# MachXO3D-QFN72-breakout.net
KiCad netlist of a schematic drawn in Altium Designer
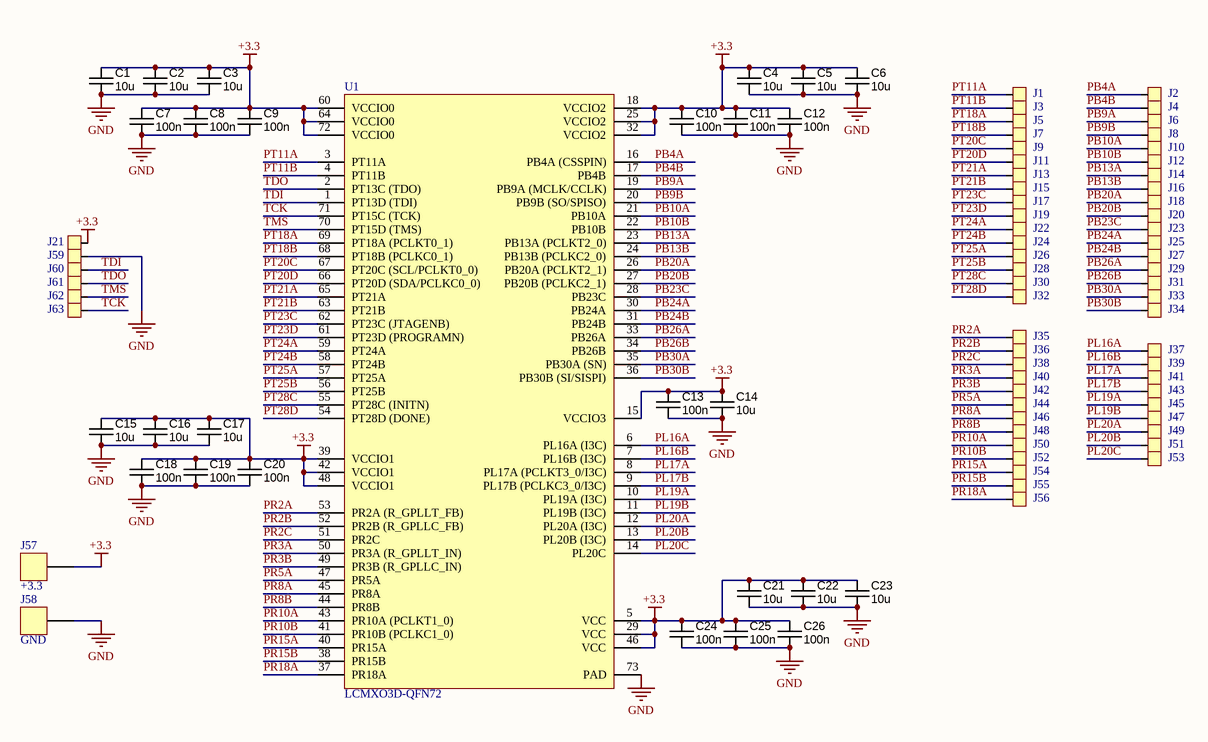
[diagram p0: MachXO3D-QFN72-breakout.SchDoc]

(export (version "E")
  (design (tool "Eeschema 10.0.6"))
  (components
    (comp (ref "C1")
      (value "10u")
      (footprint "CAPC1005X55N")
      (description "Capacitor SMD Cer 1uF 10% 16V X5R 0402")
      (fields (field (name "TOLERANCE") "±10%"))
      (libsource (lib "PBL - Capacitors") (part "CAPC_1u_0402_X5R_6V3_10%"))
    )
    (comp (ref "C2")
      (value "10u")
      (footprint "CAPC1005X55N")
      (description "Capacitor SMD Cer 1uF 10% 16V X5R 0402")
      (fields (field (name "TOLERANCE") "±10%"))
      (libsource (lib "PBL - Capacitors") (part "CAPC_1u_0402_X5R_6V3_10%"))
    )
    (comp (ref "C3")
      (value "10u")
      (footprint "CAPC1005X55N")
      (description "Capacitor SMD Cer 1uF 10% 16V X5R 0402")
      (fields (field (name "TOLERANCE") "±10%"))
      (libsource (lib "PBL - Capacitors") (part "CAPC_1u_0402_X5R_6V3_10%"))
    )
    (comp (ref "C4")
      (value "10u")
      (footprint "CAPC1005X55N")
      (description "Capacitor SMD Cer 1uF 10% 16V X5R 0402")
      (fields (field (name "TOLERANCE") "±10%"))
      (libsource (lib "PBL - Capacitors") (part "CAPC_1u_0402_X5R_6V3_10%"))
    )
    (comp (ref "C5")
      (value "10u")
      (footprint "CAPC1005X55N")
      (description "Capacitor SMD Cer 1uF 10% 16V X5R 0402")
      (fields (field (name "TOLERANCE") "±10%"))
      (libsource (lib "PBL - Capacitors") (part "CAPC_1u_0402_X5R_6V3_10%"))
    )
    (comp (ref "C6")
      (value "10u")
      (footprint "CAPC1005X55N")
      (description "Capacitor SMD Cer 1uF 10% 16V X5R 0402")
      (fields (field (name "TOLERANCE") "±10%"))
      (libsource (lib "PBL - Capacitors") (part "CAPC_1u_0402_X5R_6V3_10%"))
    )
    (comp (ref "C7")
      (value "100n")
      (footprint "CAPC0603X04N")
      (fields (field (name "Comment") "CAPC_100n_0201"))
      (libsource (lib "passive") (part "CAPC_100n_0201"))
    )
    (comp (ref "C8")
      (value "100n")
      (footprint "CAPC0603X04N")
      (fields (field (name "Comment") "CAPC_100n_0201"))
      (libsource (lib "passive") (part "CAPC_100n_0201"))
    )
    (comp (ref "C9")
      (value "100n")
      (footprint "CAPC0603X04N")
      (fields (field (name "Comment") "CAPC_100n_0201"))
      (libsource (lib "passive") (part "CAPC_100n_0201"))
    )
    (comp (ref "C10")
      (value "100n")
      (footprint "CAPC0603X04N")
      (fields (field (name "Comment") "CAPC_100n_0201"))
      (libsource (lib "passive") (part "CAPC_100n_0201"))
    )
    (comp (ref "C11")
      (value "100n")
      (footprint "CAPC0603X04N")
      (fields (field (name "Comment") "CAPC_100n_0201"))
      (libsource (lib "passive") (part "CAPC_100n_0201"))
    )
    (comp (ref "C12")
      (value "100n")
      (footprint "CAPC0603X04N")
      (fields (field (name "Comment") "CAPC_100n_0201"))
      (libsource (lib "passive") (part "CAPC_100n_0201"))
    )
    (comp (ref "C13")
      (value "100n")
      (footprint "CAPC0603X04N")
      (fields (field (name "Comment") "CAPC_100n_0201"))
      (libsource (lib "passive") (part "CAPC_100n_0201"))
    )
    (comp (ref "C14")
      (value "10u")
      (footprint "CAPC1005X55N")
      (description "Capacitor SMD Cer 1uF 10% 16V X5R 0402")
      (fields (field (name "TOLERANCE") "±10%"))
      (libsource (lib "PBL - Capacitors") (part "CAPC_1u_0402_X5R_6V3_10%"))
    )
    (comp (ref "C15")
      (value "10u")
      (footprint "CAPC1005X55N")
      (description "Capacitor SMD Cer 1uF 10% 16V X5R 0402")
      (fields (field (name "TOLERANCE") "±10%"))
      (libsource (lib "PBL - Capacitors") (part "CAPC_1u_0402_X5R_6V3_10%"))
    )
    (comp (ref "C16")
      (value "10u")
      (footprint "CAPC1005X55N")
      (description "Capacitor SMD Cer 1uF 10% 16V X5R 0402")
      (fields (field (name "TOLERANCE") "±10%"))
      (libsource (lib "PBL - Capacitors") (part "CAPC_1u_0402_X5R_6V3_10%"))
    )
    (comp (ref "C17")
      (value "10u")
      (footprint "CAPC1005X55N")
      (description "Capacitor SMD Cer 1uF 10% 16V X5R 0402")
      (fields (field (name "TOLERANCE") "±10%"))
      (libsource (lib "PBL - Capacitors") (part "CAPC_1u_0402_X5R_6V3_10%"))
    )
    (comp (ref "C18")
      (value "100n")
      (footprint "CAPC0603X04N")
      (fields (field (name "Comment") "CAPC_100n_0201"))
      (libsource (lib "passive") (part "CAPC_100n_0201"))
    )
    (comp (ref "C19")
      (value "100n")
      (footprint "CAPC0603X04N")
      (fields (field (name "Comment") "CAPC_100n_0201"))
      (libsource (lib "passive") (part "CAPC_100n_0201"))
    )
    (comp (ref "C20")
      (value "100n")
      (footprint "CAPC0603X04N")
      (fields (field (name "Comment") "CAPC_100n_0201"))
      (libsource (lib "passive") (part "CAPC_100n_0201"))
    )
    (comp (ref "C21")
      (value "10u")
      (footprint "CAPC1005X55N")
      (description "Capacitor SMD Cer 1uF 10% 16V X5R 0402")
      (fields (field (name "TOLERANCE") "±10%"))
      (libsource (lib "PBL - Capacitors") (part "CAPC_1u_0402_X5R_6V3_10%"))
    )
    (comp (ref "C22")
      (value "10u")
      (footprint "CAPC1005X55N")
      (description "Capacitor SMD Cer 1uF 10% 16V X5R 0402")
      (fields (field (name "TOLERANCE") "±10%"))
      (libsource (lib "PBL - Capacitors") (part "CAPC_1u_0402_X5R_6V3_10%"))
    )
    (comp (ref "C23")
      (value "10u")
      (footprint "CAPC1005X55N")
      (description "Capacitor SMD Cer 1uF 10% 16V X5R 0402")
      (fields (field (name "TOLERANCE") "±10%"))
      (libsource (lib "PBL - Capacitors") (part "CAPC_1u_0402_X5R_6V3_10%"))
    )
    (comp (ref "C24")
      (value "100n")
      (footprint "CAPC0603X04N")
      (fields (field (name "Comment") "CAPC_100n_0201"))
      (libsource (lib "passive") (part "CAPC_100n_0201"))
    )
    (comp (ref "C25")
      (value "100n")
      (footprint "CAPC0603X04N")
      (fields (field (name "Comment") "CAPC_100n_0201"))
      (libsource (lib "passive") (part "CAPC_100n_0201"))
    )
    (comp (ref "C26")
      (value "100n")
      (footprint "CAPC0603X04N")
      (fields (field (name "Comment") "CAPC_100n_0201"))
      (libsource (lib "passive") (part "CAPC_100n_0201"))
    )
    (comp (ref "J1") (value "T11A") (footprint "PAD-1020") (libsource (lib "connectors") (part "SOLDER-PAD")))
    (comp (ref "J2") (value "B4A") (footprint "PAD-1020") (libsource (lib "connectors") (part "SOLDER-PAD")))
    (comp (ref "J3") (value "T11B") (footprint "PAD-1020") (libsource (lib "connectors") (part "SOLDER-PAD")))
    (comp (ref "J4") (value "B4B") (footprint "PAD-1020") (libsource (lib "connectors") (part "SOLDER-PAD")))
    (comp (ref "J5") (value "T18A") (footprint "PAD-1020") (libsource (lib "connectors") (part "SOLDER-PAD")))
    (comp (ref "J6") (value "B9A") (footprint "PAD-1020") (libsource (lib "connectors") (part "SOLDER-PAD")))
    (comp (ref "J7") (value "T18B") (footprint "PAD-1020") (libsource (lib "connectors") (part "SOLDER-PAD")))
    (comp (ref "J8") (value "B9B") (footprint "PAD-1020") (libsource (lib "connectors") (part "SOLDER-PAD")))
    (comp (ref "J9") (value "T20C") (footprint "PAD-1020") (libsource (lib "connectors") (part "SOLDER-PAD")))
    (comp (ref "J10")
      (value "B10A")
      (footprint "PAD-1020")
      (libsource (lib "connectors") (part "SOLDER-PAD"))
    )
    (comp (ref "J11")
      (value "T20D")
      (footprint "PAD-1020")
      (libsource (lib "connectors") (part "SOLDER-PAD"))
    )
    (comp (ref "J12")
      (value "B10B")
      (footprint "PAD-1020")
      (libsource (lib "connectors") (part "SOLDER-PAD"))
    )
    (comp (ref "J13")
      (value "T21A")
      (footprint "PAD-1020")
      (libsource (lib "connectors") (part "SOLDER-PAD"))
    )
    (comp (ref "J14")
      (value "B13A")
      (footprint "PAD-1020")
      (libsource (lib "connectors") (part "SOLDER-PAD"))
    )
    (comp (ref "J15")
      (value "T21B")
      (footprint "PAD-1020")
      (libsource (lib "connectors") (part "SOLDER-PAD"))
    )
    (comp (ref "J16")
      (value "B13B")
      (footprint "PAD-1020")
      (libsource (lib "connectors") (part "SOLDER-PAD"))
    )
    (comp (ref "J17")
      (value "T23C")
      (footprint "PAD-1020")
      (libsource (lib "connectors") (part "SOLDER-PAD"))
    )
    (comp (ref "J18")
      (value "B20A")
      (footprint "PAD-1020")
      (libsource (lib "connectors") (part "SOLDER-PAD"))
    )
    (comp (ref "J19")
      (value "T23D")
      (footprint "PAD-1020")
      (libsource (lib "connectors") (part "SOLDER-PAD"))
    )
    (comp (ref "J20")
      (value "B20B")
      (footprint "PAD-1020")
      (libsource (lib "connectors") (part "SOLDER-PAD"))
    )
    (comp (ref "J21") (value "+3.3") (footprint "PAD-1020") (libsource (lib "") (part "SOLDER-PAD_1")))
    (comp (ref "J22")
      (value "T24A")
      (footprint "PAD-1020")
      (libsource (lib "connectors") (part "SOLDER-PAD"))
    )
    (comp (ref "J23")
      (value "B23C")
      (footprint "PAD-1020")
      (libsource (lib "connectors") (part "SOLDER-PAD"))
    )
    (comp (ref "J24")
      (value "T24B")
      (footprint "PAD-1020")
      (libsource (lib "connectors") (part "SOLDER-PAD"))
    )
    (comp (ref "J25")
      (value "B24A")
      (footprint "PAD-1020")
      (libsource (lib "connectors") (part "SOLDER-PAD"))
    )
    (comp (ref "J26")
      (value "T25A")
      (footprint "PAD-1020")
      (libsource (lib "connectors") (part "SOLDER-PAD"))
    )
    (comp (ref "J27")
      (value "B24B")
      (footprint "PAD-1020")
      (libsource (lib "connectors") (part "SOLDER-PAD"))
    )
    (comp (ref "J28")
      (value "T25B")
      (footprint "PAD-1020")
      (libsource (lib "connectors") (part "SOLDER-PAD"))
    )
    (comp (ref "J29")
      (value "B26A")
      (footprint "PAD-1020")
      (libsource (lib "connectors") (part "SOLDER-PAD"))
    )
    (comp (ref "J30")
      (value "T28C")
      (footprint "PAD-1020")
      (libsource (lib "connectors") (part "SOLDER-PAD"))
    )
    (comp (ref "J31")
      (value "B26B")
      (footprint "PAD-1020")
      (libsource (lib "connectors") (part "SOLDER-PAD"))
    )
    (comp (ref "J32")
      (value "T28D")
      (footprint "PAD-1020")
      (libsource (lib "connectors") (part "SOLDER-PAD"))
    )
    (comp (ref "J33")
      (value "B30A")
      (footprint "PAD-1020")
      (libsource (lib "connectors") (part "SOLDER-PAD"))
    )
    (comp (ref "J34")
      (value "B30B")
      (footprint "PAD-1020")
      (libsource (lib "connectors") (part "SOLDER-PAD"))
    )
    (comp (ref "J35") (value "R2A") (footprint "PAD-1020") (libsource (lib "connectors") (part "SOLDER-PAD")))
    (comp (ref "J36") (value "R2B") (footprint "PAD-1020") (libsource (lib "connectors") (part "SOLDER-PAD")))
    (comp (ref "J37")
      (value "L16A")
      (footprint "PAD-1020")
      (libsource (lib "connectors") (part "SOLDER-PAD"))
    )
    (comp (ref "J38") (value "R2C") (footprint "PAD-1020") (libsource (lib "connectors") (part "SOLDER-PAD")))
    (comp (ref "J39")
      (value "L16B")
      (footprint "PAD-1020")
      (libsource (lib "connectors") (part "SOLDER-PAD"))
    )
    (comp (ref "J40") (value "R3A") (footprint "PAD-1020") (libsource (lib "connectors") (part "SOLDER-PAD")))
    (comp (ref "J41")
      (value "L17A")
      (footprint "PAD-1020")
      (libsource (lib "connectors") (part "SOLDER-PAD"))
    )
    (comp (ref "J42") (value "R3A") (footprint "PAD-1020") (libsource (lib "connectors") (part "SOLDER-PAD")))
    (comp (ref "J43")
      (value "L17B")
      (footprint "PAD-1020")
      (libsource (lib "connectors") (part "SOLDER-PAD"))
    )
    (comp (ref "J44") (value "R5A") (footprint "PAD-1020") (libsource (lib "connectors") (part "SOLDER-PAD")))
    (comp (ref "J45")
      (value "L19A")
      (footprint "PAD-1020")
      (libsource (lib "connectors") (part "SOLDER-PAD"))
    )
    (comp (ref "J46") (value "R8A") (footprint "PAD-1020") (libsource (lib "connectors") (part "SOLDER-PAD")))
    (comp (ref "J47")
      (value "L19B")
      (footprint "PAD-1020")
      (libsource (lib "connectors") (part "SOLDER-PAD"))
    )
    (comp (ref "J48") (value "R8B") (footprint "PAD-1020") (libsource (lib "connectors") (part "SOLDER-PAD")))
    (comp (ref "J49")
      (value "L20A")
      (footprint "PAD-1020")
      (libsource (lib "connectors") (part "SOLDER-PAD"))
    )
    (comp (ref "J50")
      (value "R10A")
      (footprint "PAD-1020")
      (libsource (lib "connectors") (part "SOLDER-PAD"))
    )
    (comp (ref "J51")
      (value "L20B")
      (footprint "PAD-1020")
      (libsource (lib "connectors") (part "SOLDER-PAD"))
    )
    (comp (ref "J52")
      (value "R10B")
      (footprint "PAD-1020")
      (libsource (lib "connectors") (part "SOLDER-PAD"))
    )
    (comp (ref "J53")
      (value "L20C")
      (footprint "PAD-1020")
      (libsource (lib "connectors") (part "SOLDER-PAD"))
    )
    (comp (ref "J54")
      (value "R15A")
      (footprint "PAD-1020")
      (libsource (lib "connectors") (part "SOLDER-PAD"))
    )
    (comp (ref "J55")
      (value "R15B")
      (footprint "PAD-1020")
      (libsource (lib "connectors") (part "SOLDER-PAD"))
    )
    (comp (ref "J56")
      (value "R18A")
      (footprint "PAD-1020")
      (libsource (lib "connectors") (part "SOLDER-PAD"))
    )
    (comp (ref "J57")
      (value "+3.3")
      (footprint "POWER-PAD-4x3")
      (libsource (lib "connectors") (part "HEADER-1"))
    )
    (comp (ref "J58")
      (value "GND")
      (footprint "POWER-PAD-4x3")
      (libsource (lib "connectors") (part "HEADER-1"))
    )
    (comp (ref "J59") (value "GND") (footprint "PAD-1020") (libsource (lib "") (part "SOLDER-PAD_1")))
    (comp (ref "J60") (value "TDI") (footprint "PAD-1020") (libsource (lib "") (part "SOLDER-PAD_1")))
    (comp (ref "J61") (value "TDO") (footprint "PAD-1020") (libsource (lib "") (part "SOLDER-PAD_1")))
    (comp (ref "J62") (value "TMS") (footprint "PAD-1020") (libsource (lib "") (part "SOLDER-PAD_1")))
    (comp (ref "J63") (value "TCK") (footprint "PAD-1020") (libsource (lib "") (part "SOLDER-PAD_1")))
    (comp (ref "U1")
      (value "LCMXO3D-QFN72")
      (footprint "MachXO3D-QFN72")
      (libsource (lib "lattice") (part "LCMXO3D-QFN72"))
    )
  )
  (nets
    (net (code "1") (name "+3.3") (class "Default")
      (node (ref "C1") (pin "1") (pintype "passive"))
      (node (ref "C10") (pin "2") (pinfunction "2_2") (pintype "passive"))
      (node (ref "C11") (pin "2") (pinfunction "2_2") (pintype "passive"))
      (node (ref "C12") (pin "2") (pinfunction "2_2") (pintype "passive"))
      (node (ref "C13") (pin "2") (pinfunction "2_2") (pintype "passive"))
      (node (ref "C14") (pin "1") (pintype "passive"))
      (node (ref "C15") (pin "1") (pintype "passive"))
      (node (ref "C16") (pin "1") (pintype "passive"))
      (node (ref "C17") (pin "1") (pintype "passive"))
      (node (ref "C18") (pin "2") (pinfunction "2_2") (pintype "passive"))
      (node (ref "C19") (pin "2") (pinfunction "2_2") (pintype "passive"))
      (node (ref "C2") (pin "1") (pintype "passive"))
      (node (ref "C20") (pin "2") (pinfunction "2_2") (pintype "passive"))
      (node (ref "C21") (pin "1") (pintype "passive"))
      (node (ref "C22") (pin "1") (pintype "passive"))
      (node (ref "C23") (pin "1") (pintype "passive"))
      (node (ref "C24") (pin "2") (pinfunction "2_2") (pintype "passive"))
      (node (ref "C25") (pin "2") (pinfunction "2_2") (pintype "passive"))
      (node (ref "C26") (pin "2") (pinfunction "2_2") (pintype "passive"))
      (node (ref "C3") (pin "1") (pintype "passive"))
      (node (ref "C4") (pin "1") (pintype "passive"))
      (node (ref "C5") (pin "1") (pintype "passive"))
      (node (ref "C6") (pin "1") (pintype "passive"))
      (node (ref "C7") (pin "2") (pinfunction "2_2") (pintype "passive"))
      (node (ref "C8") (pin "2") (pinfunction "2_2") (pintype "passive"))
      (node (ref "C9") (pin "2") (pinfunction "2_2") (pintype "passive"))
      (node (ref "J21") (pin "1") (pinfunction "1_1") (pintype "passive"))
      (node (ref "J57") (pin "1") (pinfunction "1_1") (pintype "passive"))
      (node (ref "U1") (pin "15") (pinfunction "VCCIO3_15") (pintype "passive"))
      (node (ref "U1") (pin "18") (pinfunction "VCCIO2_18") (pintype "passive"))
      (node (ref "U1") (pin "25") (pinfunction "VCCIO2_25") (pintype "passive"))
      (node (ref "U1") (pin "29") (pinfunction "VCC_29") (pintype "passive"))
      (node (ref "U1") (pin "32") (pinfunction "VCCIO2_32") (pintype "passive"))
      (node (ref "U1") (pin "39") (pinfunction "VCCIO1_39") (pintype "passive"))
      (node (ref "U1") (pin "42") (pinfunction "VCCIO1_42") (pintype "passive"))
      (node (ref "U1") (pin "46") (pinfunction "VCC_46") (pintype "passive"))
      (node (ref "U1") (pin "48") (pinfunction "VCCIO1_48") (pintype "passive"))
      (node (ref "U1") (pin "5") (pinfunction "VCC_5") (pintype "passive"))
      (node (ref "U1") (pin "60") (pinfunction "VCCIO0_60") (pintype "passive"))
      (node (ref "U1") (pin "64") (pinfunction "VCCIO0_64") (pintype "passive"))
      (node (ref "U1") (pin "72") (pinfunction "VCCIO0_72") (pintype "passive"))
    )
    (net (code "2") (name "/PB4A") (class "Default")
      (node (ref "J2") (pin "1") (pinfunction "1_1") (pintype "passive"))
      (node (ref "U1") (pin "16") (pinfunction "PB4A_(CSSPIN)_16") (pintype "passive"))
    )
    (net (code "3") (name "/PB4B") (class "Default")
      (node (ref "J4") (pin "1") (pinfunction "1_1") (pintype "passive"))
      (node (ref "U1") (pin "17") (pinfunction "PB4B_17") (pintype "passive"))
    )
    (net (code "4") (name "/PB9A") (class "Default")
      (node (ref "J6") (pin "1") (pinfunction "1_1") (pintype "passive"))
      (node (ref "U1") (pin "19") (pinfunction "PB9A_(MCLK/CCLK)_19") (pintype "passive"))
    )
    (net (code "5") (name "/PB9B") (class "Default")
      (node (ref "J8") (pin "1") (pinfunction "1_1") (pintype "passive"))
      (node (ref "U1") (pin "20") (pinfunction "PB9B_(SO/SPISO)_20") (pintype "passive"))
    )
    (net (code "6") (name "/PB10A") (class "Default")
      (node (ref "J10") (pin "1") (pinfunction "1_1") (pintype "passive"))
      (node (ref "U1") (pin "21") (pinfunction "PB10A_21") (pintype "passive"))
    )
    (net (code "7") (name "/PB10B") (class "Default")
      (node (ref "J12") (pin "1") (pinfunction "1_1") (pintype "passive"))
      (node (ref "U1") (pin "22") (pinfunction "PB10B_22") (pintype "passive"))
    )
    (net (code "8") (name "/PB13A") (class "Default")
      (node (ref "J14") (pin "1") (pinfunction "1_1") (pintype "passive"))
      (node (ref "U1") (pin "23") (pinfunction "PB13A_(PCLKT2_0)_23") (pintype "passive"))
    )
    (net (code "9") (name "/PB13B") (class "Default")
      (node (ref "J16") (pin "1") (pinfunction "1_1") (pintype "passive"))
      (node (ref "U1") (pin "24") (pinfunction "PB13B_(PCLKC2_0)_24") (pintype "passive"))
    )
    (net (code "10") (name "/PB20A") (class "Default")
      (node (ref "J18") (pin "1") (pinfunction "1_1") (pintype "passive"))
      (node (ref "U1") (pin "26") (pinfunction "PB20A_(PCLKT2_1)_26") (pintype "passive"))
    )
    (net (code "11") (name "/PB20B") (class "Default")
      (node (ref "J20") (pin "1") (pinfunction "1_1") (pintype "passive"))
      (node (ref "U1") (pin "27") (pinfunction "PB20B_(PCLKC2_1)_27") (pintype "passive"))
    )
    (net (code "12") (name "/PB23C") (class "Default")
      (node (ref "J23") (pin "1") (pinfunction "1_1") (pintype "passive"))
      (node (ref "U1") (pin "28") (pinfunction "PB23C_28") (pintype "passive"))
    )
    (net (code "13") (name "/PB24A") (class "Default")
      (node (ref "J25") (pin "1") (pinfunction "1_1") (pintype "passive"))
      (node (ref "U1") (pin "30") (pinfunction "PB24A_30") (pintype "passive"))
    )
    (net (code "14") (name "/PB24B") (class "Default")
      (node (ref "J27") (pin "1") (pinfunction "1_1") (pintype "passive"))
      (node (ref "U1") (pin "31") (pinfunction "PB24B_31") (pintype "passive"))
    )
    (net (code "15") (name "/PB26A") (class "Default")
      (node (ref "J29") (pin "1") (pinfunction "1_1") (pintype "passive"))
      (node (ref "U1") (pin "33") (pinfunction "PB26A_33") (pintype "passive"))
    )
    (net (code "16") (name "/PB26B") (class "Default")
      (node (ref "J31") (pin "1") (pinfunction "1_1") (pintype "passive"))
      (node (ref "U1") (pin "34") (pinfunction "PB26B_34") (pintype "passive"))
    )
    (net (code "17") (name "/PB30A") (class "Default")
      (node (ref "J33") (pin "1") (pinfunction "1_1") (pintype "passive"))
      (node (ref "U1") (pin "35") (pinfunction "PB30A_(SN)_35") (pintype "passive"))
    )
    (net (code "18") (name "/PB30B") (class "Default")
      (node (ref "J34") (pin "1") (pinfunction "1_1") (pintype "passive"))
      (node (ref "U1") (pin "36") (pinfunction "PB30B_(SI/SISPI)_36") (pintype "passive"))
    )
    (net (code "19") (name "/PL16A") (class "Default")
      (node (ref "J37") (pin "1") (pinfunction "1_1") (pintype "passive"))
      (node (ref "U1") (pin "6") (pinfunction "PL16A_(I3C)_6") (pintype "passive"))
    )
    (net (code "20") (name "/PL16B") (class "Default")
      (node (ref "J39") (pin "1") (pinfunction "1_1") (pintype "passive"))
      (node (ref "U1") (pin "7") (pinfunction "PL16B_(I3C)_7") (pintype "passive"))
    )
    (net (code "21") (name "/PL17A") (class "Default")
      (node (ref "J41") (pin "1") (pinfunction "1_1") (pintype "passive"))
      (node (ref "U1") (pin "8") (pinfunction "PL17A_(PCLKT3_0/I3C)_8") (pintype "passive"))
    )
    (net (code "22") (name "/PL17B") (class "Default")
      (node (ref "J43") (pin "1") (pinfunction "1_1") (pintype "passive"))
      (node (ref "U1") (pin "9") (pinfunction "PL17B_(PCLKC3_0/I3C)_9") (pintype "passive"))
    )
    (net (code "23") (name "/PL19A") (class "Default")
      (node (ref "J45") (pin "1") (pinfunction "1_1") (pintype "passive"))
      (node (ref "U1") (pin "10") (pinfunction "PL19A_(I3C)_10") (pintype "passive"))
    )
    (net (code "24") (name "/PL19B") (class "Default")
      (node (ref "J47") (pin "1") (pinfunction "1_1") (pintype "passive"))
      (node (ref "U1") (pin "11") (pinfunction "PL19B_(I3C)_11") (pintype "passive"))
    )
    (net (code "25") (name "/PL20A") (class "Default")
      (node (ref "J49") (pin "1") (pinfunction "1_1") (pintype "passive"))
      (node (ref "U1") (pin "12") (pinfunction "PL20A_(I3C)_12") (pintype "passive"))
    )
    (net (code "26") (name "/PL20B") (class "Default")
      (node (ref "J51") (pin "1") (pinfunction "1_1") (pintype "passive"))
      (node (ref "U1") (pin "13") (pinfunction "PL20B_(I3C)_13") (pintype "passive"))
    )
    (net (code "27") (name "/PL20C") (class "Default")
      (node (ref "J53") (pin "1") (pinfunction "1_1") (pintype "passive"))
      (node (ref "U1") (pin "14") (pinfunction "PL20C_14") (pintype "passive"))
    )
    (net (code "28") (name "/PR2A") (class "Default")
      (node (ref "J35") (pin "1") (pinfunction "1_1") (pintype "passive"))
      (node (ref "U1") (pin "53") (pinfunction "PR2A_(R_GPLLT_FB)_53") (pintype "passive"))
    )
    (net (code "29") (name "/PR2B") (class "Default")
      (node (ref "J36") (pin "1") (pinfunction "1_1") (pintype "passive"))
      (node (ref "U1") (pin "52") (pinfunction "PR2B_(R_GPLLC_FB)_52") (pintype "passive"))
    )
    (net (code "30") (name "/PR2C") (class "Default")
      (node (ref "J38") (pin "1") (pinfunction "1_1") (pintype "passive"))
      (node (ref "U1") (pin "51") (pinfunction "PR2C_51") (pintype "passive"))
    )
    (net (code "31") (name "/PR3A") (class "Default")
      (node (ref "J40") (pin "1") (pinfunction "1_1") (pintype "passive"))
      (node (ref "U1") (pin "50") (pinfunction "PR3A_(R_GPLLT_IN)_50") (pintype "passive"))
    )
    (net (code "32") (name "/PR3B") (class "Default")
      (node (ref "J42") (pin "1") (pinfunction "1_1") (pintype "passive"))
      (node (ref "U1") (pin "49") (pinfunction "PR3B_(R_GPLLC_IN)_49") (pintype "passive"))
    )
    (net (code "33") (name "/PR5A") (class "Default")
      (node (ref "J44") (pin "1") (pinfunction "1_1") (pintype "passive"))
      (node (ref "U1") (pin "47") (pinfunction "PR5A_47") (pintype "passive"))
    )
    (net (code "34") (name "/PR8A") (class "Default")
      (node (ref "J46") (pin "1") (pinfunction "1_1") (pintype "passive"))
      (node (ref "U1") (pin "45") (pinfunction "PR8A_45") (pintype "passive"))
    )
    (net (code "35") (name "/PR8B") (class "Default")
      (node (ref "J48") (pin "1") (pinfunction "1_1") (pintype "passive"))
      (node (ref "U1") (pin "44") (pinfunction "PR8B_44") (pintype "passive"))
    )
    (net (code "36") (name "/PR10A") (class "Default")
      (node (ref "J50") (pin "1") (pinfunction "1_1") (pintype "passive"))
      (node (ref "U1") (pin "43") (pinfunction "PR10A_(PCLKT1_0)_43") (pintype "passive"))
    )
    (net (code "37") (name "/PR10B") (class "Default")
      (node (ref "J52") (pin "1") (pinfunction "1_1") (pintype "passive"))
      (node (ref "U1") (pin "41") (pinfunction "PR10B_(PCLKC1_0)_41") (pintype "passive"))
    )
    (net (code "38") (name "/PR15A") (class "Default")
      (node (ref "J54") (pin "1") (pinfunction "1_1") (pintype "passive"))
      (node (ref "U1") (pin "40") (pinfunction "PR15A_40") (pintype "passive"))
    )
    (net (code "39") (name "/PR15B") (class "Default")
      (node (ref "J55") (pin "1") (pinfunction "1_1") (pintype "passive"))
      (node (ref "U1") (pin "38") (pinfunction "PR15B_38") (pintype "passive"))
    )
    (net (code "40") (name "/PR18A") (class "Default")
      (node (ref "J56") (pin "1") (pinfunction "1_1") (pintype "passive"))
      (node (ref "U1") (pin "37") (pinfunction "PR18A_37") (pintype "passive"))
    )
    (net (code "41") (name "/PT11A") (class "Default")
      (node (ref "J1") (pin "1") (pinfunction "1_1") (pintype "passive"))
      (node (ref "U1") (pin "3") (pinfunction "PT11A_3") (pintype "passive"))
    )
    (net (code "42") (name "/PT11B") (class "Default")
      (node (ref "J3") (pin "1") (pinfunction "1_1") (pintype "passive"))
      (node (ref "U1") (pin "4") (pinfunction "PT11B_4") (pintype "passive"))
    )
    (net (code "43") (name "/PT18A") (class "Default")
      (node (ref "J5") (pin "1") (pinfunction "1_1") (pintype "passive"))
      (node (ref "U1") (pin "69") (pinfunction "PT18A_(PCLKT0_1)_69") (pintype "passive"))
    )
    (net (code "44") (name "/PT18B") (class "Default")
      (node (ref "J7") (pin "1") (pinfunction "1_1") (pintype "passive"))
      (node (ref "U1") (pin "68") (pinfunction "PT18B_(PCLKC0_1)_68") (pintype "passive"))
    )
    (net (code "45") (name "/PT20C") (class "Default")
      (node (ref "J9") (pin "1") (pinfunction "1_1") (pintype "passive"))
      (node (ref "U1") (pin "67") (pinfunction "PT20C_(SCL/PCLKT0_0)_67") (pintype "passive"))
    )
    (net (code "46") (name "/PT20D") (class "Default")
      (node (ref "J11") (pin "1") (pinfunction "1_1") (pintype "passive"))
      (node (ref "U1") (pin "66") (pinfunction "PT20D_(SDA/PCLKC0_0)_66") (pintype "passive"))
    )
    (net (code "47") (name "/PT21A") (class "Default")
      (node (ref "J13") (pin "1") (pinfunction "1_1") (pintype "passive"))
      (node (ref "U1") (pin "65") (pinfunction "PT21A_65") (pintype "passive"))
    )
    (net (code "48") (name "/PT21B") (class "Default")
      (node (ref "J15") (pin "1") (pinfunction "1_1") (pintype "passive"))
      (node (ref "U1") (pin "63") (pinfunction "PT21B_63") (pintype "passive"))
    )
    (net (code "49") (name "/PT23C") (class "Default")
      (node (ref "J17") (pin "1") (pinfunction "1_1") (pintype "passive"))
      (node (ref "U1") (pin "62") (pinfunction "PT23C_(JTAGENB)_62") (pintype "passive"))
    )
    (net (code "50") (name "/PT23D") (class "Default")
      (node (ref "J19") (pin "1") (pinfunction "1_1") (pintype "passive"))
      (node (ref "U1") (pin "61") (pinfunction "PT23D_(PROGRAMN)_61") (pintype "passive"))
    )
    (net (code "51") (name "/PT24A") (class "Default")
      (node (ref "J22") (pin "1") (pinfunction "1_1") (pintype "passive"))
      (node (ref "U1") (pin "59") (pinfunction "PT24A_59") (pintype "passive"))
    )
    (net (code "52") (name "/PT24B") (class "Default")
      (node (ref "J24") (pin "1") (pinfunction "1_1") (pintype "passive"))
      (node (ref "U1") (pin "58") (pinfunction "PT24B_58") (pintype "passive"))
    )
    (net (code "53") (name "/PT25A") (class "Default")
      (node (ref "J26") (pin "1") (pinfunction "1_1") (pintype "passive"))
      (node (ref "U1") (pin "57") (pinfunction "PT25A_57") (pintype "passive"))
    )
    (net (code "54") (name "/PT25B") (class "Default")
      (node (ref "J28") (pin "1") (pinfunction "1_1") (pintype "passive"))
      (node (ref "U1") (pin "56") (pinfunction "PT25B_56") (pintype "passive"))
    )
    (net (code "55") (name "/PT28C") (class "Default")
      (node (ref "J30") (pin "1") (pinfunction "1_1") (pintype "passive"))
      (node (ref "U1") (pin "55") (pinfunction "PT28C_(INITN)_55") (pintype "passive"))
    )
    (net (code "56") (name "/PT28D") (class "Default")
      (node (ref "J32") (pin "1") (pinfunction "1_1") (pintype "passive"))
      (node (ref "U1") (pin "54") (pinfunction "PT28D_(DONE)_54") (pintype "passive"))
    )
    (net (code "57") (name "/TCK") (class "Default")
      (node (ref "J63") (pin "1") (pinfunction "1_1") (pintype "passive"))
      (node (ref "U1") (pin "71") (pinfunction "PT15C_(TCK)_71") (pintype "passive"))
    )
    (net (code "58") (name "/TDI") (class "Default")
      (node (ref "J60") (pin "1") (pinfunction "1_1") (pintype "passive"))
      (node (ref "U1") (pin "1") (pinfunction "PT13D_(TDI)_1") (pintype "passive"))
    )
    (net (code "59") (name "/TDO") (class "Default")
      (node (ref "J61") (pin "1") (pinfunction "1_1") (pintype "passive"))
      (node (ref "U1") (pin "2") (pinfunction "PT13C_(TDO)_2") (pintype "passive"))
    )
    (net (code "60") (name "/TMS") (class "Default")
      (node (ref "J62") (pin "1") (pinfunction "1_1") (pintype "passive"))
      (node (ref "U1") (pin "70") (pinfunction "PT15D_(TMS)_70") (pintype "passive"))
    )
    (net (code "61") (name "GND") (class "Default")
      (node (ref "C1") (pin "2") (pintype "passive"))
      (node (ref "C10") (pin "1") (pinfunction "1_1") (pintype "passive"))
      (node (ref "C11") (pin "1") (pinfunction "1_1") (pintype "passive"))
      (node (ref "C12") (pin "1") (pinfunction "1_1") (pintype "passive"))
      (node (ref "C13") (pin "1") (pinfunction "1_1") (pintype "passive"))
      (node (ref "C14") (pin "2") (pintype "passive"))
      (node (ref "C15") (pin "2") (pintype "passive"))
      (node (ref "C16") (pin "2") (pintype "passive"))
      (node (ref "C17") (pin "2") (pintype "passive"))
      (node (ref "C18") (pin "1") (pinfunction "1_1") (pintype "passive"))
      (node (ref "C19") (pin "1") (pinfunction "1_1") (pintype "passive"))
      (node (ref "C2") (pin "2") (pintype "passive"))
      (node (ref "C20") (pin "1") (pinfunction "1_1") (pintype "passive"))
      (node (ref "C21") (pin "2") (pintype "passive"))
      (node (ref "C22") (pin "2") (pintype "passive"))
      (node (ref "C23") (pin "2") (pintype "passive"))
      (node (ref "C24") (pin "1") (pinfunction "1_1") (pintype "passive"))
      (node (ref "C25") (pin "1") (pinfunction "1_1") (pintype "passive"))
      (node (ref "C26") (pin "1") (pinfunction "1_1") (pintype "passive"))
      (node (ref "C3") (pin "2") (pintype "passive"))
      (node (ref "C4") (pin "2") (pintype "passive"))
      (node (ref "C5") (pin "2") (pintype "passive"))
      (node (ref "C6") (pin "2") (pintype "passive"))
      (node (ref "C7") (pin "1") (pinfunction "1_1") (pintype "passive"))
      (node (ref "C8") (pin "1") (pinfunction "1_1") (pintype "passive"))
      (node (ref "C9") (pin "1") (pinfunction "1_1") (pintype "passive"))
      (node (ref "J58") (pin "1") (pinfunction "1_1") (pintype "passive"))
      (node (ref "J59") (pin "1") (pinfunction "1_1") (pintype "passive"))
      (node (ref "U1") (pin "73") (pinfunction "PAD_73") (pintype "passive"))
    )
  )
)
